# -Key.net
KiCad netlist of a schematic drawn in Altium Designer
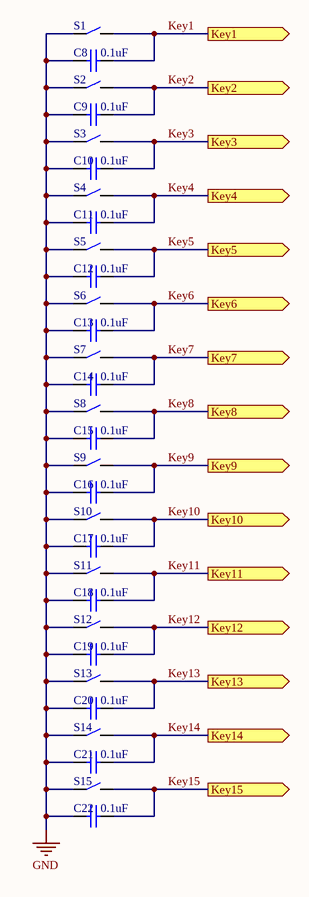
[diagram p0: 电子脚铐便携式主控板-Key.SchDoc]

(export (version "E")
  (design (tool "Eeschema 10.0.6"))
  (components
    (comp (ref "C8") (value "0.1uF") (footprint "C0603") (libsource (lib "RLCYDF") (part "Cap Semi")))
    (comp (ref "C9") (value "0.1uF") (footprint "C0603") (libsource (lib "RLCYDF") (part "Cap Semi")))
    (comp (ref "C10") (value "0.1uF") (footprint "C0603") (libsource (lib "RLCYDF") (part "Cap Semi")))
    (comp (ref "C11") (value "0.1uF") (footprint "C0603") (libsource (lib "RLCYDF") (part "Cap Semi")))
    (comp (ref "C12") (value "0.1uF") (footprint "C0603") (libsource (lib "RLCYDF") (part "Cap Semi")))
    (comp (ref "C13") (value "0.1uF") (footprint "C0603") (libsource (lib "RLCYDF") (part "Cap Semi")))
    (comp (ref "C14") (value "0.1uF") (footprint "C0603") (libsource (lib "RLCYDF") (part "Cap Semi")))
    (comp (ref "C15") (value "0.1uF") (footprint "C0603") (libsource (lib "RLCYDF") (part "Cap Semi")))
    (comp (ref "C16") (value "0.1uF") (footprint "C0603") (libsource (lib "RLCYDF") (part "Cap Semi")))
    (comp (ref "C17") (value "0.1uF") (footprint "C0603") (libsource (lib "RLCYDF") (part "Cap Semi")))
    (comp (ref "C18") (value "0.1uF") (footprint "C0603") (libsource (lib "RLCYDF") (part "Cap Semi")))
    (comp (ref "C19") (value "0.1uF") (footprint "C0603") (libsource (lib "RLCYDF") (part "Cap Semi")))
    (comp (ref "C20") (value "0.1uF") (footprint "C0603") (libsource (lib "RLCYDF") (part "Cap Semi")))
    (comp (ref "C21") (value "0.1uF") (footprint "C0603") (libsource (lib "RLCYDF") (part "Cap Semi")))
    (comp (ref "C22") (value "0.1uF") (footprint "C0603") (libsource (lib "RLCYDF") (part "Cap Semi")))
    (comp (ref "S1") (value "Switch") (footprint "B3F-4055") (libsource (lib "Connector") (part "Sw")))
    (comp (ref "S2") (value "Switch") (footprint "B3F-4055") (libsource (lib "Connector") (part "Sw")))
    (comp (ref "S3") (value "Switch") (footprint "B3F-4055") (libsource (lib "Connector") (part "Sw")))
    (comp (ref "S4") (value "Switch") (footprint "B3F-4055") (libsource (lib "Connector") (part "Sw")))
    (comp (ref "S5") (value "Switch") (footprint "B3F-4055") (libsource (lib "Connector") (part "Sw")))
    (comp (ref "S6") (value "Switch") (footprint "B3F-4055") (libsource (lib "Connector") (part "Sw")))
    (comp (ref "S7") (value "Switch") (footprint "B3F-4055") (libsource (lib "Connector") (part "Sw")))
    (comp (ref "S8") (value "Switch") (footprint "B3F-4055") (libsource (lib "Connector") (part "Sw")))
    (comp (ref "S9") (value "Switch") (footprint "B3F-4055") (libsource (lib "Connector") (part "Sw")))
    (comp (ref "S10") (value "Switch") (footprint "B3F-4055") (libsource (lib "Connector") (part "Sw")))
    (comp (ref "S11") (value "Switch") (footprint "B3F-4055") (libsource (lib "Connector") (part "Sw")))
    (comp (ref "S12") (value "Switch") (footprint "B3F-4055") (libsource (lib "Connector") (part "Sw")))
    (comp (ref "S13") (value "Switch") (footprint "B3F-4055") (libsource (lib "Connector") (part "Sw")))
    (comp (ref "S14") (value "Switch") (footprint "B3F-4055") (libsource (lib "Connector") (part "Sw")))
    (comp (ref "S15") (value "Switch") (footprint "B3F-4055") (libsource (lib "Connector") (part "Sw")))
  )
  (nets
    (net (code "1") (name "/Key1") (class "Default")
      (node (ref "C8") (pin "1") (pinfunction "1_1") (pintype "passive"))
      (node (ref "S1") (pin "2") (pinfunction "2_2") (pintype "passive"))
    )
    (net (code "2") (name "/Key2") (class "Default")
      (node (ref "C9") (pin "1") (pinfunction "1_1") (pintype "passive"))
      (node (ref "S2") (pin "2") (pinfunction "2_2") (pintype "passive"))
    )
    (net (code "3") (name "/Key3") (class "Default")
      (node (ref "C10") (pin "1") (pinfunction "1_1") (pintype "passive"))
      (node (ref "S3") (pin "2") (pinfunction "2_2") (pintype "passive"))
    )
    (net (code "4") (name "/Key4") (class "Default")
      (node (ref "C11") (pin "1") (pinfunction "1_1") (pintype "passive"))
      (node (ref "S4") (pin "2") (pinfunction "2_2") (pintype "passive"))
    )
    (net (code "5") (name "/Key5") (class "Default")
      (node (ref "C12") (pin "1") (pinfunction "1_1") (pintype "passive"))
      (node (ref "S5") (pin "2") (pinfunction "2_2") (pintype "passive"))
    )
    (net (code "6") (name "/Key6") (class "Default")
      (node (ref "C13") (pin "1") (pinfunction "1_1") (pintype "passive"))
      (node (ref "S6") (pin "2") (pinfunction "2_2") (pintype "passive"))
    )
    (net (code "7") (name "/Key7") (class "Default")
      (node (ref "C14") (pin "1") (pinfunction "1_1") (pintype "passive"))
      (node (ref "S7") (pin "2") (pinfunction "2_2") (pintype "passive"))
    )
    (net (code "8") (name "/Key8") (class "Default")
      (node (ref "C15") (pin "1") (pinfunction "1_1") (pintype "passive"))
      (node (ref "S8") (pin "2") (pinfunction "2_2") (pintype "passive"))
    )
    (net (code "9") (name "/Key9") (class "Default")
      (node (ref "C16") (pin "1") (pinfunction "1_1") (pintype "passive"))
      (node (ref "S9") (pin "2") (pinfunction "2_2") (pintype "passive"))
    )
    (net (code "10") (name "/Key10") (class "Default")
      (node (ref "C17") (pin "1") (pinfunction "1_1") (pintype "passive"))
      (node (ref "S10") (pin "2") (pinfunction "2_2") (pintype "passive"))
    )
    (net (code "11") (name "/Key11") (class "Default")
      (node (ref "C18") (pin "1") (pinfunction "1_1") (pintype "passive"))
      (node (ref "S11") (pin "2") (pinfunction "2_2") (pintype "passive"))
    )
    (net (code "12") (name "/Key12") (class "Default")
      (node (ref "C19") (pin "1") (pinfunction "1_1") (pintype "passive"))
      (node (ref "S12") (pin "2") (pinfunction "2_2") (pintype "passive"))
    )
    (net (code "13") (name "/Key13") (class "Default")
      (node (ref "C20") (pin "1") (pinfunction "1_1") (pintype "passive"))
      (node (ref "S13") (pin "2") (pinfunction "2_2") (pintype "passive"))
    )
    (net (code "14") (name "/Key14") (class "Default")
      (node (ref "C21") (pin "1") (pinfunction "1_1") (pintype "passive"))
      (node (ref "S14") (pin "2") (pinfunction "2_2") (pintype "passive"))
    )
    (net (code "15") (name "/Key15") (class "Default")
      (node (ref "C22") (pin "1") (pinfunction "1_1") (pintype "passive"))
      (node (ref "S15") (pin "2") (pinfunction "2_2") (pintype "passive"))
    )
    (net (code "16") (name "GND") (class "Default")
      (node (ref "C10") (pin "2") (pinfunction "2_2") (pintype "passive"))
      (node (ref "C11") (pin "2") (pinfunction "2_2") (pintype "passive"))
      (node (ref "C12") (pin "2") (pinfunction "2_2") (pintype "passive"))
      (node (ref "C13") (pin "2") (pinfunction "2_2") (pintype "passive"))
      (node (ref "C14") (pin "2") (pinfunction "2_2") (pintype "passive"))
      (node (ref "C15") (pin "2") (pinfunction "2_2") (pintype "passive"))
      (node (ref "C16") (pin "2") (pinfunction "2_2") (pintype "passive"))
      (node (ref "C17") (pin "2") (pinfunction "2_2") (pintype "passive"))
      (node (ref "C18") (pin "2") (pinfunction "2_2") (pintype "passive"))
      (node (ref "C19") (pin "2") (pinfunction "2_2") (pintype "passive"))
      (node (ref "C20") (pin "2") (pinfunction "2_2") (pintype "passive"))
      (node (ref "C21") (pin "2") (pinfunction "2_2") (pintype "passive"))
      (node (ref "C22") (pin "2") (pinfunction "2_2") (pintype "passive"))
      (node (ref "C8") (pin "2") (pinfunction "2_2") (pintype "passive"))
      (node (ref "C9") (pin "2") (pinfunction "2_2") (pintype "passive"))
      (node (ref "S1") (pin "1") (pinfunction "1_1") (pintype "passive"))
      (node (ref "S10") (pin "1") (pinfunction "1_1") (pintype "passive"))
      (node (ref "S11") (pin "1") (pinfunction "1_1") (pintype "passive"))
      (node (ref "S12") (pin "1") (pinfunction "1_1") (pintype "passive"))
      (node (ref "S13") (pin "1") (pinfunction "1_1") (pintype "passive"))
      (node (ref "S14") (pin "1") (pinfunction "1_1") (pintype "passive"))
      (node (ref "S15") (pin "1") (pinfunction "1_1") (pintype "passive"))
      (node (ref "S2") (pin "1") (pinfunction "1_1") (pintype "passive"))
      (node (ref "S3") (pin "1") (pinfunction "1_1") (pintype "passive"))
      (node (ref "S4") (pin "1") (pinfunction "1_1") (pintype "passive"))
      (node (ref "S5") (pin "1") (pinfunction "1_1") (pintype "passive"))
      (node (ref "S6") (pin "1") (pinfunction "1_1") (pintype "passive"))
      (node (ref "S7") (pin "1") (pinfunction "1_1") (pintype "passive"))
      (node (ref "S8") (pin "1") (pinfunction "1_1") (pintype "passive"))
      (node (ref "S9") (pin "1") (pinfunction "1_1") (pintype "passive"))
    )
  )
)
